# Power.net
KiCad netlist of a schematic drawn in Altium Designer
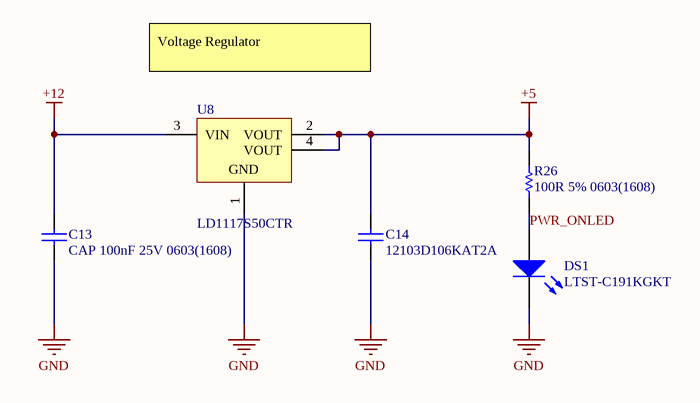
[diagram p0: Power.SchDoc]

(export (version "E")
  (design (tool "Eeschema 10.0.6"))
  (components
    (comp (ref "C13")
      (value "CAP 100nF 25V 0603(1608)")
      (footprint "CAPC0603(1608)100_N")
      (description "CAP 100nF 25V ±5% 0603 (1608 Metric) Thickness 1mm SMD")
      (fields (field (name "TOLERANCE") "Â±5%"))
      (libsource (lib "Altium Content Vault") (part "CAP"))
    )
    (comp (ref "C14")
      (value "12103D106KAT2A")
      (footprint "CAPC3225X279X50LL20T25")
      (description "Chip Capacitor, 10 uF, +/- 10%, 25 V, -55 to 85 degC, 1210 (3225 Metric), RoHS, Tape and Reel")
      (fields (field (name "TOLERANCE") "±10%") (field (name "MANUFACTURER") "AVX"))
      (libsource (lib "Altium Content Vault") (part "CAP-NP-2"))
    )
    (comp (ref "DS1")
      (value "LTST-C191KGKT")
      (footprint "LITE-ON-LTST-C191KRKT-2_V")
      (description "Chip LED, Green, 574 nm, 40 pF, -55 to 85 degC, 2-Pin SMD, RoHS, Tape and Reel")
      (fields (field (name "MANUFACTURER") "Lite-On"))
      (libsource (lib "Altium Content Vault") (part "LED-AK-2"))
    )
    (comp (ref "R26")
      (value "100R 5% 0603(1608)")
      (footprint "RESC0603(1608)_L")
      (description "100R 0.1W 5% 0603 (1608 Metric)  SMD")
      (fields (field (name "TOLERANCE") "5 %") (field (name "POWER") "0.1 W"))
      (libsource (lib "Altium Content Vault") (part "RES"))
    )
    (comp (ref "U8")
      (value "LD1117S50CTR")
      (footprint "SOT-223_N")
      (description "Fixed Low Drop Positive Voltage Regulator, 5V, 4-Pin SOT-223, Tape and Reel")
      (libsource (lib "Altium Content Vault") (part "PM-REG-LD1117-SOT4"))
    )
  )
  (nets
    (net (code "1") (name "+5") (class "Default")
      (node (ref "C14") (pin "2") (pinfunction "2_2") (pintype "passive"))
      (node (ref "R26") (pin "2") (pinfunction "2_2") (pintype "passive"))
      (node (ref "U8") (pin "2") (pinfunction "VOUT_2") (pintype "power_in"))
      (node (ref "U8") (pin "4") (pinfunction "VOUT_4") (pintype "power_in"))
    )
    (net (code "2") (name "+12") (class "Default")
      (node (ref "C13") (pin "2") (pinfunction "2_2") (pintype "passive"))
      (node (ref "U8") (pin "3") (pinfunction "VIN_3") (pintype "power_in"))
    )
    (net (code "3") (name "/PWR_ONLED") (class "Default")
      (node (ref "DS1") (pin "1") (pinfunction "A_1") (pintype "passive"))
      (node (ref "R26") (pin "1") (pinfunction "1_1") (pintype "passive"))
    )
    (net (code "4") (name "GND") (class "Default")
      (node (ref "C13") (pin "1") (pinfunction "1_1") (pintype "passive"))
      (node (ref "C14") (pin "1") (pinfunction "1_1") (pintype "passive"))
      (node (ref "DS1") (pin "2") (pinfunction "K_2") (pintype "passive"))
      (node (ref "U8") (pin "1") (pinfunction "GND_1") (pintype "power_in"))
    )
  )
)
